# SCH_555-Circuit_2025-10-19.net
KiCad netlist of a schematic drawn in EasyEDA
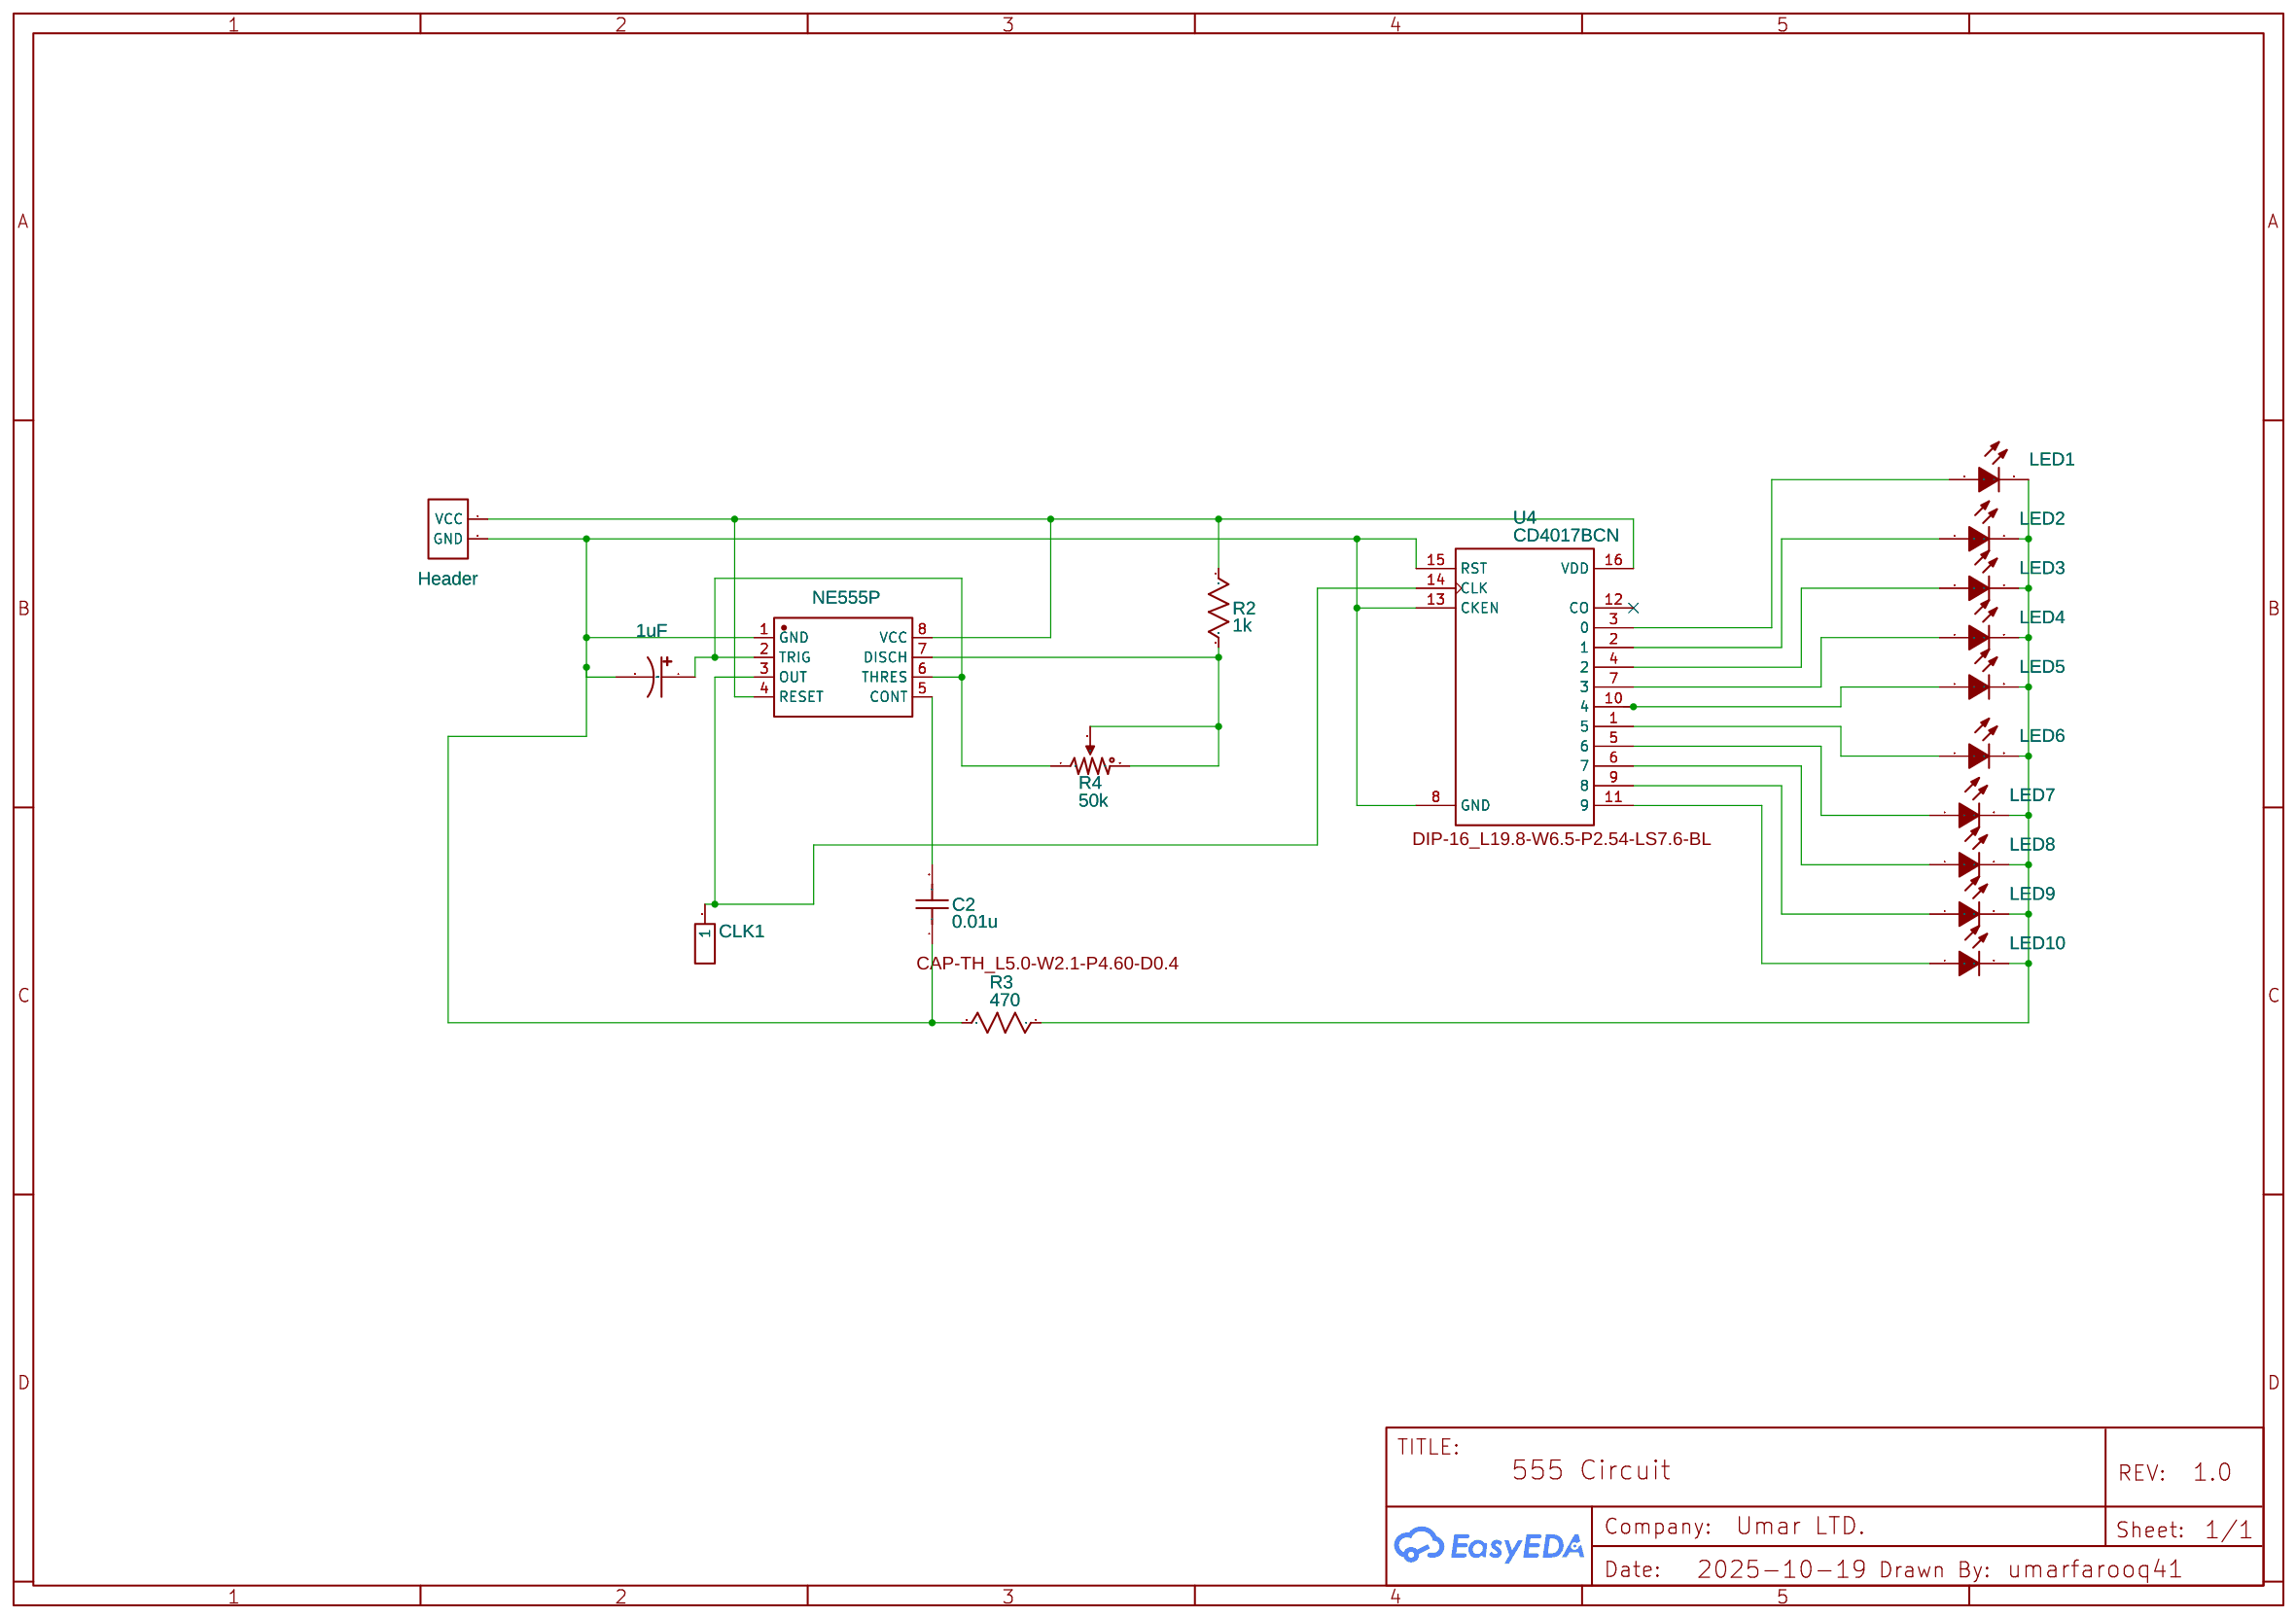
[diagram p0: schematic sheet]

(export (version "E")
  (design (tool "Eeschema 10.0.6"))
  (components
    (comp (ref "C1")
      (value "1uF")
      (fields (field (name "Manufacturer Part") "UVZ1H010MDD") (field (name "Manufacturer") "Nichicon(尼吉康)"))
      (libsource (lib "") (part "UVZ1H010MDD"))
    )
    (comp (ref "C2") (value "0.01u") (libsource (lib "") (part "C_0603_US")))
    (comp (ref "CLK1")
      (value "C81276")
      (fields
        (field (name "Manufacturer Part") "2.54-1*1P针")
        (field (name "Manufacturer") "BOOMELE(Boom Precision Elec)")
      )
      (libsource (lib "") (part "Header-Male-2.54_1x1"))
    )
    (comp (ref "H1") (value "Header") (libsource (lib "") (part "HEADER-FEMALE-2.54_1X2")))
    (comp (ref "LED1") (value "LED_5MM") (libsource (lib "") (part "LED_5MM")))
    (comp (ref "LED2") (value "LED_5MM") (libsource (lib "") (part "LED_5MM")))
    (comp (ref "LED3") (value "LED_5MM") (libsource (lib "") (part "LED_5MM")))
    (comp (ref "LED4") (value "LED_5MM") (libsource (lib "") (part "LED_5MM")))
    (comp (ref "LED5") (value "LED_5MM") (libsource (lib "") (part "LED_5MM")))
    (comp (ref "LED6") (value "LED_5MM") (libsource (lib "") (part "LED_5MM")))
    (comp (ref "LED7") (value "LED_5MM") (libsource (lib "") (part "LED_5MM")))
    (comp (ref "LED8") (value "LED_5MM") (libsource (lib "") (part "LED_5MM")))
    (comp (ref "LED9") (value "LED_5MM") (libsource (lib "") (part "LED_5MM")))
    (comp (ref "LED10") (value "LED_5MM") (libsource (lib "") (part "LED_5MM")))
    (comp (ref "R2")
      (value "1k")
      (fields (field (name "Manufacturer Part") "?"))
      (libsource (lib "") (part "Resistor"))
    )
    (comp (ref "R3")
      (value "470")
      (fields (field (name "Manufacturer Part") "?"))
      (libsource (lib "") (part "Resistor_1"))
    )
    (comp (ref "R4")
      (value "50k")
      (fields (field (name "Manufacturer Part") "?"))
      (libsource (lib "") (part "Potentiometer"))
    )
    (comp (ref "U2")
      (value "NE555P")
      (fields (field (name "Manufacturer") "TI(德州仪器)"))
      (libsource (lib "") (part "NE555P"))
    )
    (comp (ref "U4") (value "CD4017BCN") (libsource (lib "") (part "CD4017BCN")))
  )
  (nets
    (net (code "1") (name "Net-(H1-GND)") (class "Default")
      (node (ref "C1") (pin "2") (pinfunction "2_2") (pintype "unspecified"))
      (node (ref "C2") (pin "1") (pinfunction "1_1") (pintype "unspecified"))
      (node (ref "H1") (pin "2") (pinfunction "GND_2") (pintype "unspecified"))
      (node (ref "R3") (pin "2") (pinfunction "2_2") (pintype "unspecified"))
      (node (ref "U2") (pin "1") (pinfunction "GND_1") (pintype "unspecified"))
      (node (ref "U4") (pin "13") (pinfunction "CKEN_13") (pintype "unspecified"))
      (node (ref "U4") (pin "15") (pinfunction "RST_15") (pintype "unspecified"))
      (node (ref "U4") (pin "8") (pinfunction "GND_8") (pintype "passive"))
    )
    (net (code "2") (name "Net-(H1-VCC)") (class "Default")
      (node (ref "H1") (pin "1") (pinfunction "VCC_1") (pintype "unspecified"))
      (node (ref "R2") (pin "1") (pinfunction "1_1") (pintype "unspecified"))
      (node (ref "U2") (pin "4") (pinfunction "RESET_4") (pintype "unspecified"))
      (node (ref "U2") (pin "8") (pinfunction "VCC_8") (pintype "unspecified"))
      (node (ref "U4") (pin "16") (pinfunction "VDD_16") (pintype "passive"))
    )
    (net (code "3") (name "Net-(LED1-A)") (class "Default")
      (node (ref "LED1") (pin "1") (pinfunction "A_1") (pintype "input"))
      (node (ref "U4") (pin "3") (pinfunction "0_3") (pintype "output"))
    )
    (net (code "4") (name "Net-(LED1-K)") (class "Default")
      (node (ref "LED1") (pin "2") (pinfunction "K_2") (pintype "input"))
      (node (ref "LED10") (pin "2") (pinfunction "K_2") (pintype "input"))
      (node (ref "LED2") (pin "2") (pinfunction "K_2") (pintype "input"))
      (node (ref "LED3") (pin "2") (pinfunction "K_2") (pintype "input"))
      (node (ref "LED4") (pin "2") (pinfunction "K_2") (pintype "input"))
      (node (ref "LED5") (pin "2") (pinfunction "K_2") (pintype "input"))
      (node (ref "LED6") (pin "2") (pinfunction "K_2") (pintype "input"))
      (node (ref "LED7") (pin "2") (pinfunction "K_2") (pintype "input"))
      (node (ref "LED8") (pin "2") (pinfunction "K_2") (pintype "input"))
      (node (ref "LED9") (pin "2") (pinfunction "K_2") (pintype "input"))
      (node (ref "R3") (pin "1") (pinfunction "1_1") (pintype "unspecified"))
    )
    (net (code "5") (name "Net-(LED2-A)") (class "Default")
      (node (ref "LED2") (pin "1") (pinfunction "A_1") (pintype "input"))
      (node (ref "U4") (pin "2") (pinfunction "1_2") (pintype "output"))
    )
    (net (code "6") (name "Net-(LED3-A)") (class "Default")
      (node (ref "LED3") (pin "1") (pinfunction "A_1") (pintype "input"))
      (node (ref "U4") (pin "4") (pinfunction "2_4") (pintype "output"))
    )
    (net (code "7") (name "Net-(LED4-A)") (class "Default")
      (node (ref "LED4") (pin "1") (pinfunction "A_1") (pintype "input"))
      (node (ref "U4") (pin "7") (pinfunction "3_7") (pintype "output"))
    )
    (net (code "8") (name "Net-(LED5-A)") (class "Default")
      (node (ref "LED5") (pin "1") (pinfunction "A_1") (pintype "input"))
      (node (ref "U4") (pin "10") (pinfunction "4_10") (pintype "output"))
    )
    (net (code "9") (name "Net-(LED6-A)") (class "Default")
      (node (ref "LED6") (pin "1") (pinfunction "A_1") (pintype "input"))
      (node (ref "U4") (pin "1") (pinfunction "5_1") (pintype "output"))
    )
    (net (code "10") (name "Net-(LED7-A)") (class "Default")
      (node (ref "LED7") (pin "1") (pinfunction "A_1") (pintype "input"))
      (node (ref "U4") (pin "5") (pinfunction "6_5") (pintype "output"))
    )
    (net (code "11") (name "Net-(LED8-A)") (class "Default")
      (node (ref "LED8") (pin "1") (pinfunction "A_1") (pintype "input"))
      (node (ref "U4") (pin "6") (pinfunction "7_6") (pintype "output"))
    )
    (net (code "12") (name "Net-(LED9-A)") (class "Default")
      (node (ref "LED9") (pin "1") (pinfunction "A_1") (pintype "input"))
      (node (ref "U4") (pin "9") (pinfunction "8_9") (pintype "output"))
    )
    (net (code "13") (name "Net-(LED10-A)") (class "Default")
      (node (ref "LED10") (pin "1") (pinfunction "A_1") (pintype "input"))
      (node (ref "U4") (pin "11") (pinfunction "9_11") (pintype "output"))
    )
    (net (code "14") (name "Net-(R4-2)") (class "Default")
      (node (ref "R2") (pin "2") (pinfunction "2_2") (pintype "unspecified"))
      (node (ref "R4") (pin "2") (pinfunction "3_2") (pintype "unspecified"))
      (node (ref "R4") (pin "3") (pinfunction "2_3") (pintype "unspecified"))
      (node (ref "U2") (pin "7") (pinfunction "DISCH_7") (pintype "unspecified"))
    )
    (net (code "15") (name "Net-(U2-CONT)") (class "Default")
      (node (ref "C2") (pin "2") (pinfunction "2_2") (pintype "unspecified"))
      (node (ref "U2") (pin "5") (pinfunction "CONT_5") (pintype "unspecified"))
    )
    (net (code "16") (name "Net-(U2-OUT)") (class "Default")
      (node (ref "CLK1") (pin "1") (pinfunction "1_1") (pintype "unspecified"))
      (node (ref "U2") (pin "3") (pinfunction "OUT_3") (pintype "unspecified"))
      (node (ref "U4") (pin "14") (pinfunction "CLK_14") (pintype "unspecified"))
    )
    (net (code "17") (name "Net-(U2-THRES)") (class "Default")
      (node (ref "C1") (pin "1") (pinfunction "1_1") (pintype "unspecified"))
      (node (ref "R4") (pin "1") (pinfunction "1_1") (pintype "unspecified"))
      (node (ref "U2") (pin "2") (pinfunction "TRIG_2") (pintype "unspecified"))
      (node (ref "U2") (pin "6") (pinfunction "THRES_6") (pintype "unspecified"))
    )
    (net (code "18") (name "unconnected-(U4-CO-Pad12)") (class "Default")
      (node (ref "U4") (pin "12") (pinfunction "CO_12") (pintype "output+no_connect"))
    )
  )
)
